# vetinari.net
KiCad netlist of a schematic drawn in EAGLE
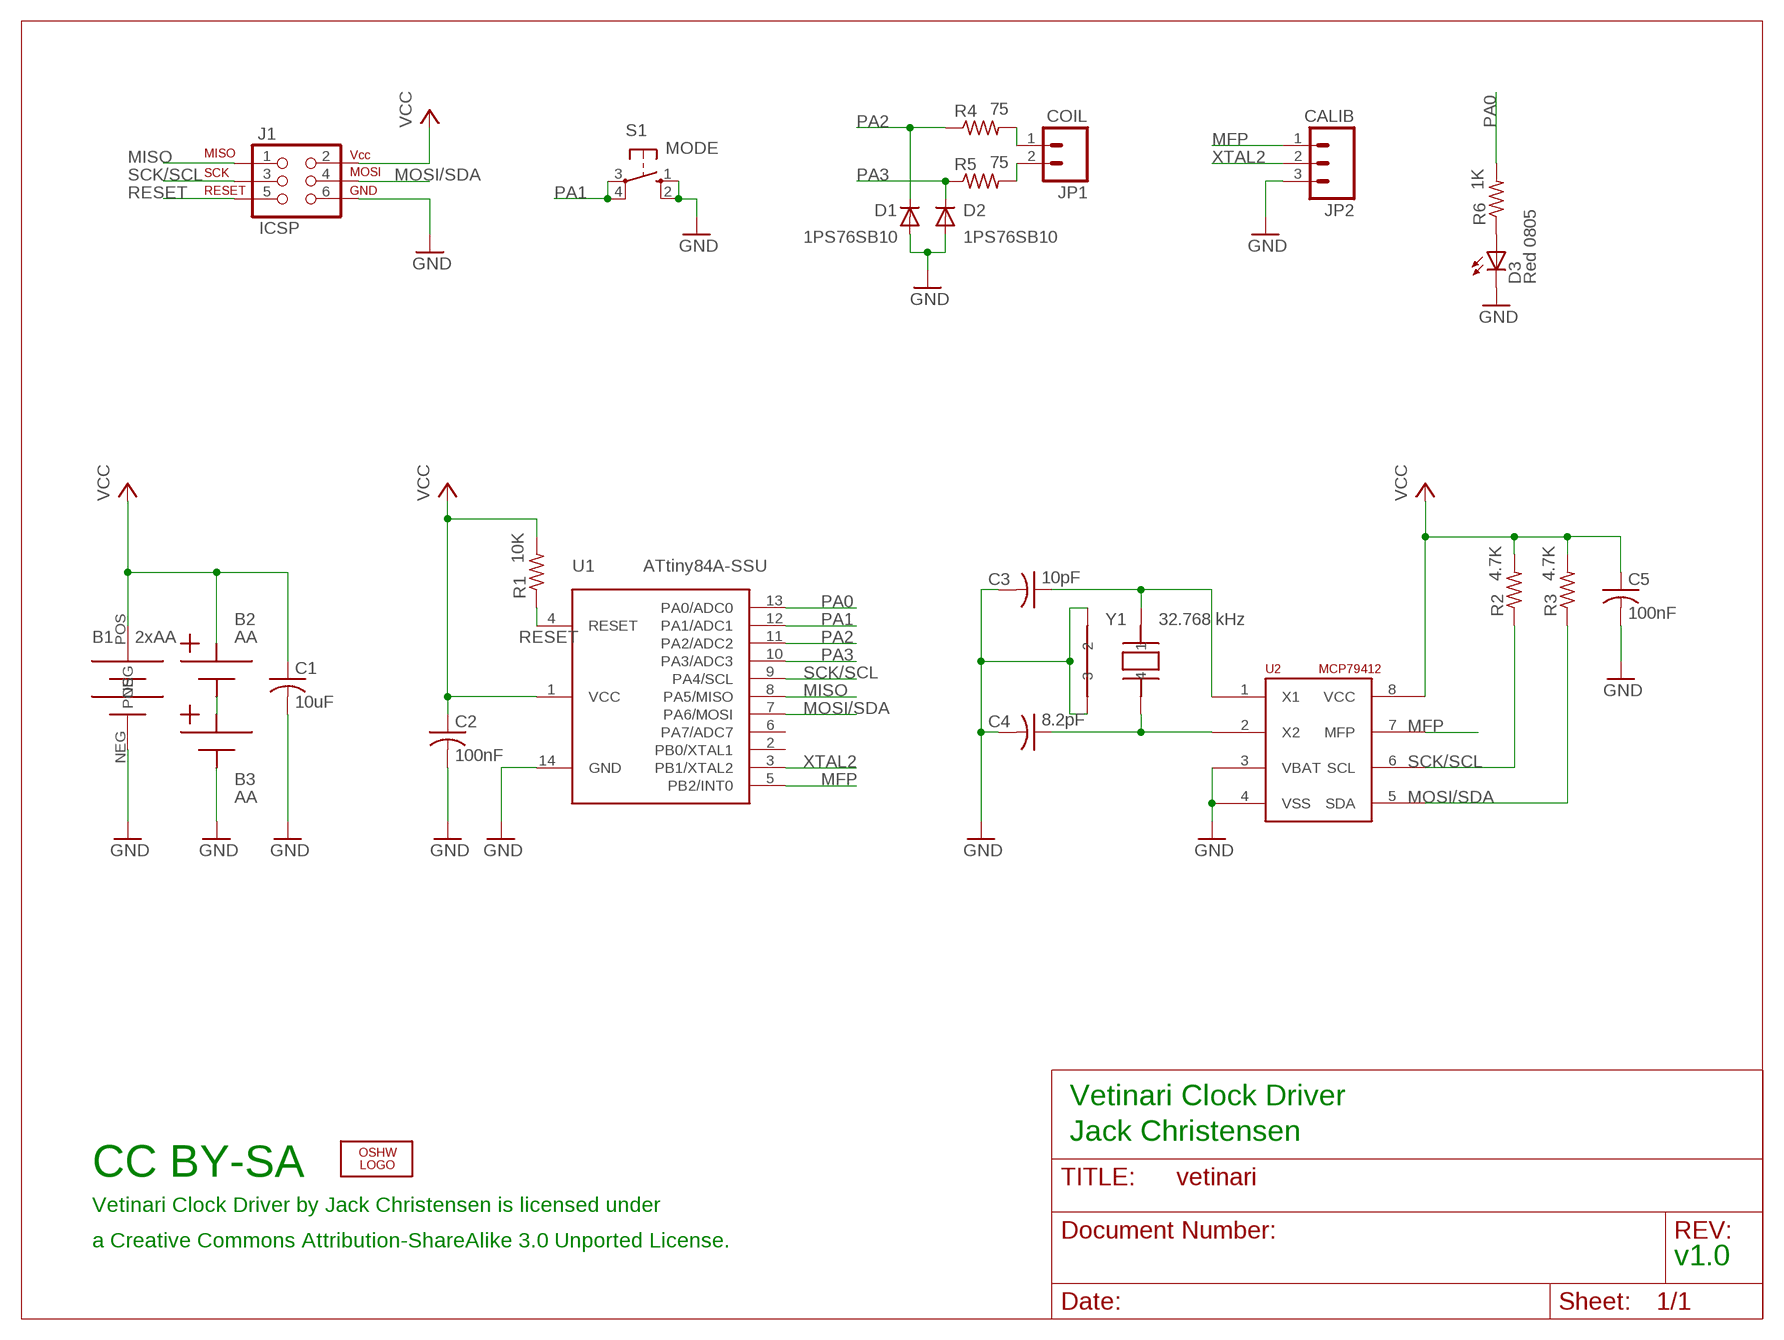
[diagram p0: schematic, sheet 1]

(export (version "E")
  (design (tool "Eeschema 10.0.6"))
  (components
    (comp (ref "B1")
      (value "2xAA")
      (footprint "eagle-import:KEYSTONE-2462-OUTLINE")
      (libsource (lib "eagle-import") (part "BATTERY-2AAOUTLINE"))
    )
    (comp (ref "B2")
      (value "AA")
      (footprint "eagle-import:BATT-AA-PC-CLIPS")
      (libsource (lib "eagle-import") (part "BATTERY-AAKEYSTONE-92"))
    )
    (comp (ref "B3")
      (value "AA")
      (footprint "eagle-import:BATT-AA-PC-CLIPS")
      (libsource (lib "eagle-import") (part "BATTERY-AAKEYSTONE-92"))
    )
    (comp (ref "C1")
      (value "10uF")
      (footprint "eagle-import:M1206")
      (libsource (lib "eagle-import") (part "C-USM1206"))
    )
    (comp (ref "C2")
      (value "100nF")
      (footprint "eagle-import:M0805")
      (libsource (lib "eagle-import") (part "C-USM0805"))
    )
    (comp (ref "C3")
      (value "10pF")
      (footprint "eagle-import:M0805")
      (libsource (lib "eagle-import") (part "C-USM0805"))
    )
    (comp (ref "C4")
      (value "8.2pF")
      (footprint "eagle-import:M0805")
      (libsource (lib "eagle-import") (part "C-USM0805"))
    )
    (comp (ref "C5")
      (value "100nF")
      (footprint "eagle-import:M0805")
      (libsource (lib "eagle-import") (part "C-USM0805"))
    )
    (comp (ref "D1")
      (value "1PS76SB10")
      (footprint "eagle-import:SOD-323F")
      (libsource (lib "eagle-import") (part "DIODESOD-323F"))
    )
    (comp (ref "D2")
      (value "1PS76SB10")
      (footprint "eagle-import:SOD-323F-A")
      (libsource (lib "eagle-import") (part "DIODESOD-323F-A"))
    )
    (comp (ref "D3")
      (value "Red 0805")
      (footprint "eagle-import:D0805")
      (libsource (lib "eagle-import") (part "LEDD0805"))
    )
    (comp (ref "J1")
      (value "ICSP")
      (footprint "eagle-import:2X3_LOCK")
      (libsource (lib "eagle-import") (part "AVR_SPI_PRG_62X3_LOCK"))
    )
    (comp (ref "JP1")
      (value "COIL")
      (footprint "eagle-import:1X02")
      (libsource (lib "eagle-import") (part "M02PTH"))
    )
    (comp (ref "JP2")
      (value "CALIB")
      (footprint "eagle-import:1X03_LOCK")
      (libsource (lib "eagle-import") (part "M03LOCK"))
    )
    (comp (ref "LOGO2")
      (value "OSHW_LOGO_8MILX0150-NT")
      (footprint "eagle-import:OSHW_8X150_NOTEXT")
      (libsource (lib "eagle-import") (part "OSHW_LOGO_8MILX0150-NT"))
    )
    (comp (ref "R1")
      (value "10K")
      (footprint "eagle-import:M0805")
      (libsource (lib "eagle-import") (part "R-US_M0805"))
    )
    (comp (ref "R2")
      (value "4.7K")
      (footprint "eagle-import:M0805")
      (libsource (lib "eagle-import") (part "R-US_M0805"))
    )
    (comp (ref "R3")
      (value "4.7K")
      (footprint "eagle-import:M0805")
      (libsource (lib "eagle-import") (part "R-US_M0805"))
    )
    (comp (ref "R4")
      (value "75")
      (footprint "eagle-import:M0805")
      (libsource (lib "eagle-import") (part "R-US_M0805"))
    )
    (comp (ref "R5")
      (value "75")
      (footprint "eagle-import:M0805")
      (libsource (lib "eagle-import") (part "R-US_M0805"))
    )
    (comp (ref "R6")
      (value "1K")
      (footprint "eagle-import:M0805")
      (libsource (lib "eagle-import") (part "R-US_M0805"))
    )
    (comp (ref "S1")
      (value "MODE")
      (footprint "eagle-import:B3F-10XXOCT")
      (libsource (lib "eagle-import") (part "10-XXOCT"))
    )
    (comp (ref "U1")
      (value "ATtiny84A-SSU")
      (footprint "eagle-import:SO14")
      (libsource (lib "eagle-import") (part "ATTINYX4SO14"))
    )
    (comp (ref "U2")
      (value "MCP79412")
      (footprint "eagle-import:SO08")
      (libsource (lib "eagle-import") (part "MCP7941X-SOIC-8"))
    )
    (comp (ref "Y1")
      (value "32.768 kHz")
      (footprint "eagle-import:CRYSTAL-CITIZEN-CM2XXC")
      (libsource (lib "eagle-import") (part "CRYSTAL-CITIZEN-CM2XXC"))
    )
  )
  (nets
    (net (code "1") (name "/MFP") (class "Default")
      (node (ref "JP2") (pin "1") (pinfunction "1_1") (pintype "passive"))
      (node (ref "U1") (pin "5") (pinfunction "PB2/INT0_5") (pintype "bidirectional"))
      (node (ref "U2") (pin "7") (pinfunction "MFP_7") (pintype "passive"))
    )
    (net (code "2") (name "/MISO") (class "Default")
      (node (ref "J1") (pin "1") (pinfunction "1_1") (pintype "passive"))
      (node (ref "U1") (pin "8") (pinfunction "PA5/MISO_8") (pintype "bidirectional"))
    )
    (net (code "3") (name "/MOSI{slash}SDA") (class "Default")
      (node (ref "J1") (pin "4") (pinfunction "4_4") (pintype "passive"))
      (node (ref "R3") (pin "1") (pinfunction "1_1") (pintype "passive"))
      (node (ref "U1") (pin "7") (pinfunction "PA6/MOSI_7") (pintype "bidirectional"))
      (node (ref "U2") (pin "5") (pinfunction "SDA_5") (pintype "passive"))
    )
    (net (code "4") (name "/PA0") (class "Default")
      (node (ref "R6") (pin "2") (pinfunction "2_2") (pintype "passive"))
      (node (ref "U1") (pin "13") (pinfunction "PA0/ADC0_13") (pintype "bidirectional"))
    )
    (net (code "5") (name "/PA1") (class "Default")
      (node (ref "S1") (pin "3") (pinfunction "P_3") (pintype "passive"))
      (node (ref "S1") (pin "4") (pinfunction "P1_4") (pintype "passive"))
      (node (ref "U1") (pin "12") (pinfunction "PA1/ADC1_12") (pintype "bidirectional"))
    )
    (net (code "6") (name "/PA2") (class "Default")
      (node (ref "D1") (pin "K") (pinfunction "K_K") (pintype "passive"))
      (node (ref "R4") (pin "1") (pinfunction "1_1") (pintype "passive"))
      (node (ref "U1") (pin "11") (pinfunction "PA2/ADC2_11") (pintype "bidirectional"))
    )
    (net (code "7") (name "/PA3") (class "Default")
      (node (ref "D2") (pin "K") (pinfunction "K_K") (pintype "passive"))
      (node (ref "R5") (pin "1") (pinfunction "1_1") (pintype "passive"))
      (node (ref "U1") (pin "10") (pinfunction "PA3/ADC3_10") (pintype "bidirectional"))
    )
    (net (code "8") (name "/RESET") (class "Default")
      (node (ref "J1") (pin "5") (pinfunction "5_5") (pintype "passive"))
      (node (ref "R1") (pin "1") (pinfunction "1_1") (pintype "passive"))
      (node (ref "U1") (pin "4") (pinfunction "RESET_4") (pintype "bidirectional"))
    )
    (net (code "9") (name "/SCK{slash}SCL") (class "Default")
      (node (ref "J1") (pin "3") (pinfunction "3_3") (pintype "passive"))
      (node (ref "R2") (pin "1") (pinfunction "1_1") (pintype "passive"))
      (node (ref "U1") (pin "9") (pinfunction "PA4/SCL_9") (pintype "bidirectional"))
      (node (ref "U2") (pin "6") (pinfunction "SCL_6") (pintype "passive"))
    )
    (net (code "10") (name "/XTAL2") (class "Default")
      (node (ref "JP2") (pin "2") (pinfunction "2_2") (pintype "passive"))
      (node (ref "U1") (pin "3") (pinfunction "PB1/XTAL2_3") (pintype "bidirectional"))
    )
    (net (code "11") (name "GND") (class "Default")
      (node (ref "B1") (pin "NEG") (pinfunction "NEG_NEG") (pintype "bidirectional"))
      (node (ref "B3") (pin "N1") (pinfunction "P$2_N1") (pintype "bidirectional"))
      (node (ref "B3") (pin "N2") (pinfunction "P$2_N2") (pintype "bidirectional"))
      (node (ref "C1") (pin "2") (pinfunction "2_2") (pintype "passive"))
      (node (ref "C2") (pin "2") (pinfunction "2_2") (pintype "passive"))
      (node (ref "C3") (pin "2") (pinfunction "2_2") (pintype "passive"))
      (node (ref "C4") (pin "2") (pinfunction "2_2") (pintype "passive"))
      (node (ref "C5") (pin "2") (pinfunction "2_2") (pintype "passive"))
      (node (ref "D1") (pin "A") (pinfunction "A_A") (pintype "passive"))
      (node (ref "D2") (pin "A") (pinfunction "A_A") (pintype "passive"))
      (node (ref "D3") (pin "K") (pinfunction "C_K") (pintype "passive"))
      (node (ref "J1") (pin "6") (pinfunction "6_6") (pintype "passive"))
      (node (ref "JP2") (pin "3") (pinfunction "3_3") (pintype "passive"))
      (node (ref "S1") (pin "1") (pinfunction "S_1") (pintype "passive"))
      (node (ref "S1") (pin "2") (pinfunction "S1_2") (pintype "passive"))
      (node (ref "U1") (pin "14") (pinfunction "GND_14") (pintype "bidirectional"))
      (node (ref "U2") (pin "3") (pinfunction "VBAT_3") (pintype "passive"))
      (node (ref "U2") (pin "4") (pinfunction "VSS_4") (pintype "passive"))
      (node (ref "Y1") (pin "P$2") (pinfunction "2_P$2") (pintype "passive"))
      (node (ref "Y1") (pin "P$3") (pinfunction "3_P$3") (pintype "passive"))
    )
    (net (code "12") (name "Net-(B2-P$2-PadN1)") (class "Default")
      (node (ref "B2") (pin "N1") (pinfunction "P$2_N1") (pintype "bidirectional"))
      (node (ref "B2") (pin "N2") (pinfunction "P$2_N2") (pintype "bidirectional"))
      (node (ref "B3") (pin "P1") (pinfunction "P$1_P1") (pintype "bidirectional"))
      (node (ref "B3") (pin "P2") (pinfunction "P$1_P2") (pintype "bidirectional"))
    )
    (net (code "13") (name "Net-(D3-PadA)") (class "Default")
      (node (ref "D3") (pin "A") (pinfunction "A_A") (pintype "passive"))
      (node (ref "R6") (pin "1") (pinfunction "1_1") (pintype "passive"))
    )
    (net (code "14") (name "Net-(JP1-Pad1)") (class "Default")
      (node (ref "JP1") (pin "1") (pinfunction "1_1") (pintype "passive"))
      (node (ref "R4") (pin "2") (pinfunction "2_2") (pintype "passive"))
    )
    (net (code "15") (name "Net-(JP1-Pad2)") (class "Default")
      (node (ref "JP1") (pin "2") (pinfunction "2_2") (pintype "passive"))
      (node (ref "R5") (pin "2") (pinfunction "2_2") (pintype "passive"))
    )
    (net (code "16") (name "Net-(U2-X1)") (class "Default")
      (node (ref "C3") (pin "1") (pinfunction "1_1") (pintype "passive"))
      (node (ref "U2") (pin "1") (pinfunction "X1_1") (pintype "passive"))
      (node (ref "Y1") (pin "P$1") (pinfunction "1_P$1") (pintype "passive"))
    )
    (net (code "17") (name "Net-(U2-X2)") (class "Default")
      (node (ref "C4") (pin "1") (pinfunction "1_1") (pintype "passive"))
      (node (ref "U2") (pin "2") (pinfunction "X2_2") (pintype "passive"))
      (node (ref "Y1") (pin "P$4") (pinfunction "4_P$4") (pintype "passive"))
    )
    (net (code "18") (name "VCC") (class "Default")
      (node (ref "B1") (pin "POS") (pinfunction "POS_POS") (pintype "bidirectional"))
      (node (ref "B2") (pin "P1") (pinfunction "P$1_P1") (pintype "bidirectional"))
      (node (ref "B2") (pin "P2") (pinfunction "P$1_P2") (pintype "bidirectional"))
      (node (ref "C1") (pin "1") (pinfunction "1_1") (pintype "passive"))
      (node (ref "C2") (pin "1") (pinfunction "1_1") (pintype "passive"))
      (node (ref "C5") (pin "1") (pinfunction "1_1") (pintype "passive"))
      (node (ref "J1") (pin "2") (pinfunction "2_2") (pintype "passive"))
      (node (ref "R1") (pin "2") (pinfunction "2_2") (pintype "passive"))
      (node (ref "R2") (pin "2") (pinfunction "2_2") (pintype "passive"))
      (node (ref "R3") (pin "2") (pinfunction "2_2") (pintype "passive"))
      (node (ref "U1") (pin "1") (pinfunction "VCC_1") (pintype "bidirectional"))
      (node (ref "U2") (pin "8") (pinfunction "VCC_8") (pintype "passive"))
    )
    (net (code "19") (name "unconnected-(U1-PA7{slash}ADC7-Pad6)") (class "Default")
      (node (ref "U1") (pin "6") (pinfunction "PA7/ADC7_6") (pintype "bidirectional"))
    )
    (net (code "20") (name "unconnected-(U1-PB0{slash}XTAL1-Pad2)") (class "Default")
      (node (ref "U1") (pin "2") (pinfunction "PB0/XTAL1_2") (pintype "bidirectional"))
    )
  )
)
